# Memory.net
KiCad netlist of a schematic drawn in Altium Designer
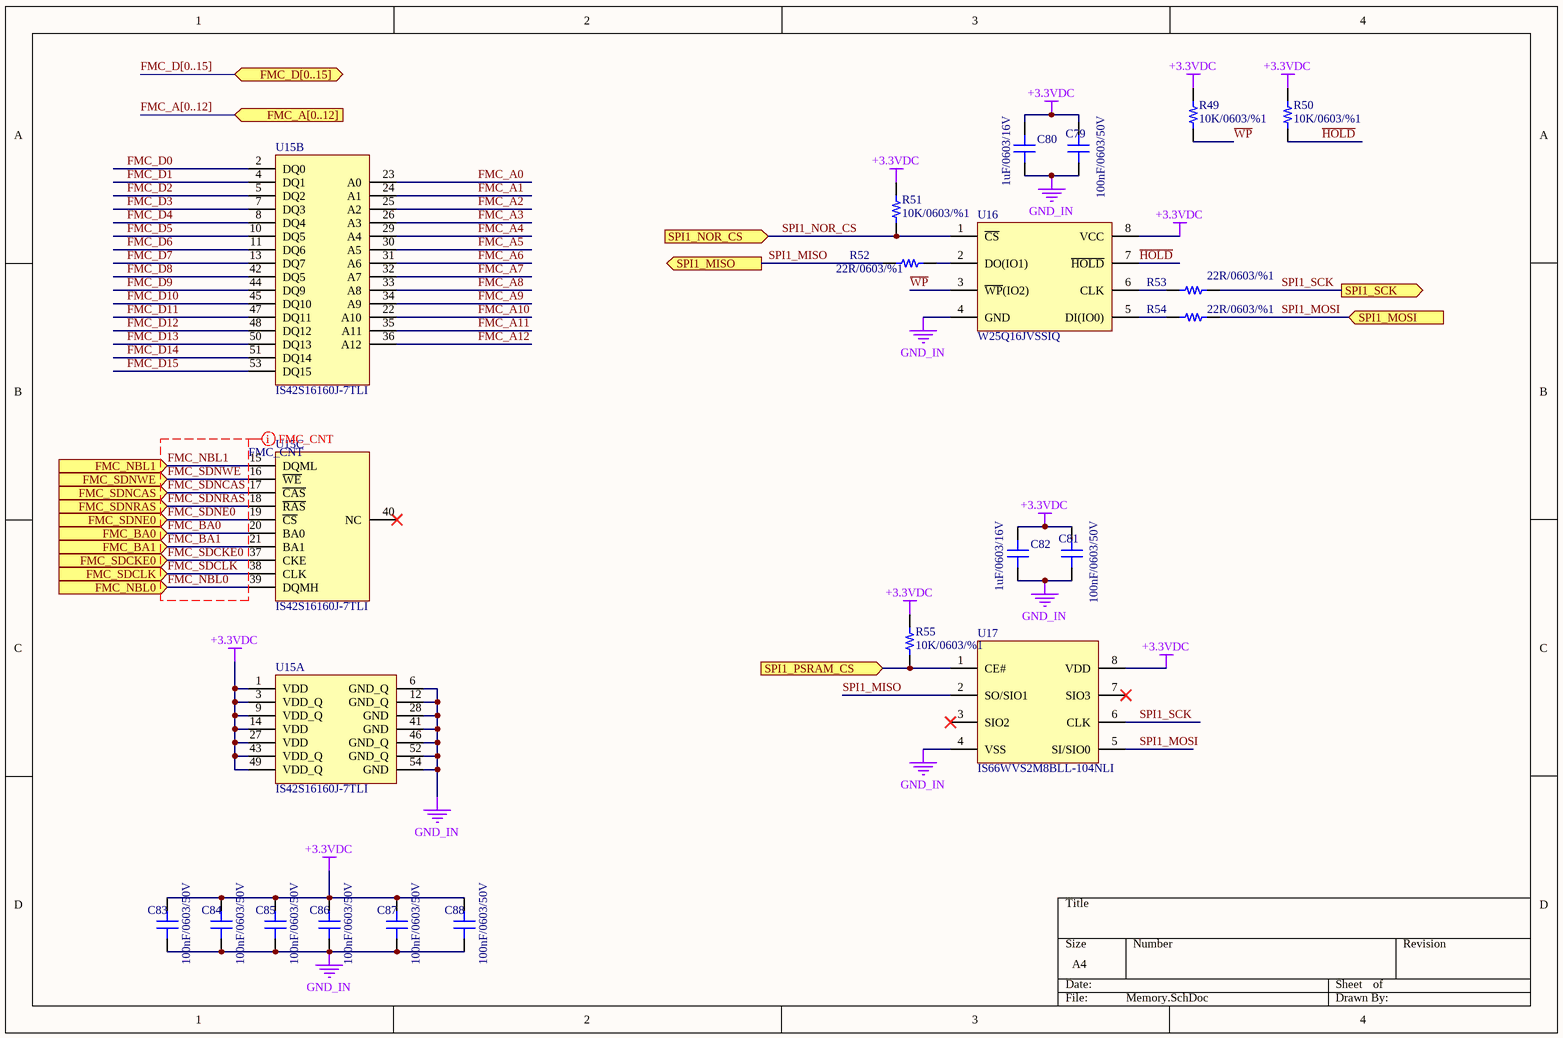
[diagram p0: Memory.SchDoc]

(export (version "E")
  (design (tool "Eeschema 10.0.6"))
  (components
    (comp (ref "C79")
      (value "100nF/0603/50V")
      (footprint "0603_cap")
      (libsource (lib "IM_v1.0") (part "Capacitor"))
    )
    (comp (ref "C80")
      (value "1uF/0603/16V")
      (footprint "0603_cap")
      (libsource (lib "IM_v1.0") (part "Capacitor"))
    )
    (comp (ref "C81")
      (value "100nF/0603/50V")
      (footprint "0603_cap")
      (libsource (lib "IM_v1.0") (part "Capacitor"))
    )
    (comp (ref "C82")
      (value "1uF/0603/16V")
      (footprint "0603_cap")
      (libsource (lib "IM_v1.0") (part "Capacitor"))
    )
    (comp (ref "C83")
      (value "100nF/0603/50V")
      (footprint "0603_cap")
      (libsource (lib "IM_v1.0") (part "Capacitor"))
    )
    (comp (ref "C84")
      (value "100nF/0603/50V")
      (footprint "0603_cap")
      (libsource (lib "IM_v1.0") (part "Capacitor"))
    )
    (comp (ref "C85")
      (value "100nF/0603/50V")
      (footprint "0603_cap")
      (libsource (lib "IM_v1.0") (part "Capacitor"))
    )
    (comp (ref "C86")
      (value "100nF/0603/50V")
      (footprint "0603_cap")
      (libsource (lib "IM_v1.0") (part "Capacitor"))
    )
    (comp (ref "C87")
      (value "100nF/0603/50V")
      (footprint "0603_cap")
      (libsource (lib "IM_v1.0") (part "Capacitor"))
    )
    (comp (ref "C88")
      (value "100nF/0603/50V")
      (footprint "0603_cap")
      (libsource (lib "IM_v1.0") (part "Capacitor"))
    )
    (comp (ref "R49") (value "10K/0603/%1") (footprint "0603_res") (libsource (lib "IM_v1.0") (part "RES")))
    (comp (ref "R50") (value "10K/0603/%1") (footprint "0603_res") (libsource (lib "IM_v1.0") (part "RES")))
    (comp (ref "R51") (value "10K/0603/%1") (footprint "0603_res") (libsource (lib "IM_v1.0") (part "RES")))
    (comp (ref "R52") (value "22R/0603/%1") (footprint "0603_res") (libsource (lib "IM_v1.0") (part "RES")))
    (comp (ref "R53") (value "22R/0603/%1") (footprint "0603_res") (libsource (lib "IM_v1.0") (part "RES")))
    (comp (ref "R54") (value "22R/0603/%1") (footprint "0603_res") (libsource (lib "IM_v1.0") (part "RES")))
    (comp (ref "R55") (value "10K/0603/%1") (footprint "0603_res") (libsource (lib "IM_v1.0") (part "RES")))
    (comp (ref "U15")
      (value "IS42S16160J-7TLI")
      (footprint "TSOP-II-54")
      (description "SDRAM Memory IC 256Mbit Parallel 143 MHz 5.4 ns 54-TSOP II")
      (libsource (lib "IM_v1.0") (part "IS42S16160J-7TLI"))
    )
    (comp (ref "U16")
      (value "W25Q16JVSSIQ")
      (footprint "8-SOIC (0.209\", 5.30mm Width)")
      (description "FLASH - NOR Memory IC 16Mbit SPI - Quad I/O 133 MHz 8-SOIC")
      (libsource (lib "IM_v1.0") (part "W25Q16JVSSIQ"))
    )
    (comp (ref "U17")
      (value "IS66WVS2M8BLL-104NLI")
      (footprint "SOIC-8(3.90MM)")
      (description "PSRAM (Pseudo SRAM) Memory IC 16Mbit SPI, QPI 104 MHz 7 ns 8-SOIC")
      (libsource (lib "IM_v1.0") (part "IS66WVS2M8BLL-104NLI"))
    )
  )
  (nets
    (net (code "1") (name "+3.3VDC") (class "Default")
      (node (ref "C79") (pin "1") (pinfunction "1_1") (pintype "passive"))
      (node (ref "C80") (pin "2") (pinfunction "2_2") (pintype "passive"))
      (node (ref "C81") (pin "1") (pinfunction "1_1") (pintype "passive"))
      (node (ref "C82") (pin "2") (pinfunction "2_2") (pintype "passive"))
      (node (ref "C83") (pin "1") (pinfunction "1_1") (pintype "passive"))
      (node (ref "C84") (pin "1") (pinfunction "1_1") (pintype "passive"))
      (node (ref "C85") (pin "1") (pinfunction "1_1") (pintype "passive"))
      (node (ref "C86") (pin "1") (pinfunction "1_1") (pintype "passive"))
      (node (ref "C87") (pin "1") (pinfunction "1_1") (pintype "passive"))
      (node (ref "C88") (pin "1") (pinfunction "1_1") (pintype "passive"))
      (node (ref "R49") (pin "1") (pinfunction "1_1") (pintype "passive"))
      (node (ref "R50") (pin "1") (pinfunction "1_1") (pintype "passive"))
      (node (ref "R51") (pin "1") (pinfunction "1_1") (pintype "passive"))
      (node (ref "R55") (pin "1") (pinfunction "1_1") (pintype "passive"))
      (node (ref "U15") (pin "1") (pinfunction "VDD_1") (pintype "passive"))
      (node (ref "U15") (pin "14") (pinfunction "VDD_14") (pintype "passive"))
      (node (ref "U15") (pin "27") (pinfunction "VDD_27") (pintype "passive"))
      (node (ref "U15") (pin "3") (pinfunction "VDD_Q_3") (pintype "passive"))
      (node (ref "U15") (pin "43") (pinfunction "VDD_Q_43") (pintype "passive"))
      (node (ref "U15") (pin "49") (pinfunction "VDD_Q_49") (pintype "passive"))
      (node (ref "U15") (pin "9") (pinfunction "VDD_Q_9") (pintype "passive"))
      (node (ref "U16") (pin "8") (pinfunction "VCC_8") (pintype "passive"))
      (node (ref "U17") (pin "8") (pinfunction "VDD_8") (pintype "passive"))
    )
    (net (code "2") (name "/FMC_A0") (class "Default")
      (node (ref "U15") (pin "23") (pinfunction "A0_23") (pintype "passive"))
    )
    (net (code "3") (name "/FMC_A1") (class "Default")
      (node (ref "U15") (pin "24") (pinfunction "A1_24") (pintype "passive"))
    )
    (net (code "4") (name "/FMC_A2") (class "Default")
      (node (ref "U15") (pin "25") (pinfunction "A2_25") (pintype "passive"))
    )
    (net (code "5") (name "/FMC_A3") (class "Default")
      (node (ref "U15") (pin "26") (pinfunction "A3_26") (pintype "passive"))
    )
    (net (code "6") (name "/FMC_A4") (class "Default")
      (node (ref "U15") (pin "29") (pinfunction "A4_29") (pintype "passive"))
    )
    (net (code "7") (name "/FMC_A5") (class "Default")
      (node (ref "U15") (pin "30") (pinfunction "A5_30") (pintype "passive"))
    )
    (net (code "8") (name "/FMC_A6") (class "Default")
      (node (ref "U15") (pin "31") (pinfunction "A6_31") (pintype "passive"))
    )
    (net (code "9") (name "/FMC_A7") (class "Default")
      (node (ref "U15") (pin "32") (pinfunction "A7_32") (pintype "passive"))
    )
    (net (code "10") (name "/FMC_A8") (class "Default")
      (node (ref "U15") (pin "33") (pinfunction "A8_33") (pintype "passive"))
    )
    (net (code "11") (name "/FMC_A9") (class "Default")
      (node (ref "U15") (pin "34") (pinfunction "A9_34") (pintype "passive"))
    )
    (net (code "12") (name "/FMC_A10") (class "Default")
      (node (ref "U15") (pin "22") (pinfunction "A10_22") (pintype "passive"))
    )
    (net (code "13") (name "/FMC_A11") (class "Default")
      (node (ref "U15") (pin "35") (pinfunction "A11_35") (pintype "passive"))
    )
    (net (code "14") (name "/FMC_A12") (class "Default")
      (node (ref "U15") (pin "36") (pinfunction "A12_36") (pintype "passive"))
    )
    (net (code "16") (name "/FMC_BA0") (class "Default")
      (node (ref "U15") (pin "20") (pinfunction "BA0_20") (pintype "passive"))
    )
    (net (code "17") (name "/FMC_BA1") (class "Default")
      (node (ref "U15") (pin "21") (pinfunction "BA1_21") (pintype "passive"))
    )
    (net (code "18") (name "/FMC_D0") (class "Default")
      (node (ref "U15") (pin "2") (pinfunction "DQ0_2") (pintype "passive"))
    )
    (net (code "19") (name "/FMC_D1") (class "Default")
      (node (ref "U15") (pin "4") (pinfunction "DQ1_4") (pintype "passive"))
    )
    (net (code "20") (name "/FMC_D2") (class "Default")
      (node (ref "U15") (pin "5") (pinfunction "DQ2_5") (pintype "passive"))
    )
    (net (code "21") (name "/FMC_D3") (class "Default")
      (node (ref "U15") (pin "7") (pinfunction "DQ3_7") (pintype "passive"))
    )
    (net (code "22") (name "/FMC_D4") (class "Default")
      (node (ref "U15") (pin "8") (pinfunction "DQ4_8") (pintype "passive"))
    )
    (net (code "23") (name "/FMC_D5") (class "Default")
      (node (ref "U15") (pin "10") (pinfunction "DQ5_10") (pintype "passive"))
    )
    (net (code "24") (name "/FMC_D6") (class "Default")
      (node (ref "U15") (pin "11") (pinfunction "DQ6_11") (pintype "passive"))
    )
    (net (code "25") (name "/FMC_D7") (class "Default")
      (node (ref "U15") (pin "13") (pinfunction "DQ7_13") (pintype "passive"))
    )
    (net (code "26") (name "/FMC_D8") (class "Default")
      (node (ref "U15") (pin "42") (pinfunction "DQ5_42") (pintype "passive"))
    )
    (net (code "27") (name "/FMC_D9") (class "Default")
      (node (ref "U15") (pin "44") (pinfunction "DQ9_44") (pintype "passive"))
    )
    (net (code "28") (name "/FMC_D10") (class "Default")
      (node (ref "U15") (pin "45") (pinfunction "DQ10_45") (pintype "passive"))
    )
    (net (code "29") (name "/FMC_D11") (class "Default")
      (node (ref "U15") (pin "47") (pinfunction "DQ11_47") (pintype "passive"))
    )
    (net (code "30") (name "/FMC_D12") (class "Default")
      (node (ref "U15") (pin "48") (pinfunction "DQ12_48") (pintype "passive"))
    )
    (net (code "31") (name "/FMC_D13") (class "Default")
      (node (ref "U15") (pin "50") (pinfunction "DQ13_50") (pintype "passive"))
    )
    (net (code "32") (name "/FMC_D14") (class "Default")
      (node (ref "U15") (pin "51") (pinfunction "DQ14_51") (pintype "passive"))
    )
    (net (code "33") (name "/FMC_D15") (class "Default")
      (node (ref "U15") (pin "53") (pinfunction "DQ15_53") (pintype "passive"))
    )
    (net (code "35") (name "/FMC_NBL0") (class "Default")
      (node (ref "U15") (pin "39") (pinfunction "DQMH_39") (pintype "passive"))
    )
    (net (code "36") (name "/FMC_NBL1") (class "Default")
      (node (ref "U15") (pin "15") (pinfunction "DQML_15") (pintype "passive"))
    )
    (net (code "37") (name "/FMC_SDCKE0") (class "Default")
      (node (ref "U15") (pin "37") (pinfunction "CKE_37") (pintype "passive"))
    )
    (net (code "38") (name "/FMC_SDCLK") (class "Default")
      (node (ref "U15") (pin "38") (pinfunction "CLK_38") (pintype "passive"))
    )
    (net (code "39") (name "/FMC_SDNCAS") (class "Default")
      (node (ref "U15") (pin "17") (pinfunction "~{CAS}_17") (pintype "passive"))
    )
    (net (code "40") (name "/FMC_SDNE0") (class "Default")
      (node (ref "U15") (pin "19") (pinfunction "~{CS}_19") (pintype "passive"))
    )
    (net (code "41") (name "/FMC_SDNRAS") (class "Default")
      (node (ref "U15") (pin "18") (pinfunction "~{RAS}_18") (pintype "passive"))
    )
    (net (code "42") (name "/FMC_SDNWE") (class "Default")
      (node (ref "U15") (pin "16") (pinfunction "~{WE}_16") (pintype "passive"))
    )
    (net (code "43") (name "/SPI1_MISO") (class "Default")
      (node (ref "R52") (pin "1") (pinfunction "1_1") (pintype "passive"))
      (node (ref "U17") (pin "2") (pinfunction "SO/SIO1_2") (pintype "passive"))
    )
    (net (code "44") (name "/SPI1_MOSI") (class "Default")
      (node (ref "R54") (pin "2") (pinfunction "2_2") (pintype "passive"))
      (node (ref "U17") (pin "5") (pinfunction "SI/SIO0_5") (pintype "passive"))
    )
    (net (code "45") (name "/SPI1_NOR_CS") (class "Default")
      (node (ref "R51") (pin "2") (pinfunction "2_2") (pintype "passive"))
      (node (ref "U16") (pin "1") (pinfunction "~{CS}_1") (pintype "passive"))
    )
    (net (code "46") (name "/SPI1_PSRAM_CS") (class "Default")
      (node (ref "R55") (pin "2") (pinfunction "2_2") (pintype "passive"))
      (node (ref "U17") (pin "1") (pinfunction "CE#_1") (pintype "passive"))
    )
    (net (code "47") (name "/SPI1_SCK") (class "Default")
      (node (ref "R53") (pin "2") (pinfunction "2_2") (pintype "passive"))
      (node (ref "U17") (pin "6") (pinfunction "CLK_6") (pintype "passive"))
    )
    (net (code "48") (name "/~{HOLD}") (class "Default")
      (node (ref "R50") (pin "2") (pinfunction "2_2") (pintype "passive"))
      (node (ref "U16") (pin "7") (pinfunction "~{HOLD}_7") (pintype "passive"))
    )
    (net (code "49") (name "/~{WP}") (class "Default")
      (node (ref "R49") (pin "2") (pinfunction "2_2") (pintype "passive"))
      (node (ref "U16") (pin "3") (pinfunction "~{WP}(IO2)_3") (pintype "passive"))
    )
    (net (code "50") (name "GND_IN") (class "Default")
      (node (ref "C79") (pin "2") (pinfunction "2_2") (pintype "passive"))
      (node (ref "C80") (pin "1") (pinfunction "1_1") (pintype "passive"))
      (node (ref "C81") (pin "2") (pinfunction "2_2") (pintype "passive"))
      (node (ref "C82") (pin "1") (pinfunction "1_1") (pintype "passive"))
      (node (ref "C83") (pin "2") (pinfunction "2_2") (pintype "passive"))
      (node (ref "C84") (pin "2") (pinfunction "2_2") (pintype "passive"))
      (node (ref "C85") (pin "2") (pinfunction "2_2") (pintype "passive"))
      (node (ref "C86") (pin "2") (pinfunction "2_2") (pintype "passive"))
      (node (ref "C87") (pin "2") (pinfunction "2_2") (pintype "passive"))
      (node (ref "C88") (pin "2") (pinfunction "2_2") (pintype "passive"))
      (node (ref "U15") (pin "12") (pinfunction "GND_Q_12") (pintype "passive"))
      (node (ref "U15") (pin "28") (pinfunction "GND_28") (pintype "passive"))
      (node (ref "U15") (pin "41") (pinfunction "GND_41") (pintype "passive"))
      (node (ref "U15") (pin "46") (pinfunction "GND_Q_46") (pintype "passive"))
      (node (ref "U15") (pin "52") (pinfunction "GND_Q_52") (pintype "passive"))
      (node (ref "U15") (pin "54") (pinfunction "GND_54") (pintype "passive"))
      (node (ref "U15") (pin "6") (pinfunction "GND_Q_6") (pintype "passive"))
      (node (ref "U16") (pin "4") (pinfunction "GND_4") (pintype "passive"))
      (node (ref "U17") (pin "4") (pinfunction "VSS_4") (pintype "passive"))
    )
    (net (code "51") (name "Net-(U16-CLK)") (class "Default")
      (node (ref "R53") (pin "1") (pinfunction "1_1") (pintype "passive"))
      (node (ref "U16") (pin "6") (pinfunction "CLK_6") (pintype "passive"))
    )
    (net (code "52") (name "Net-(U16-DI(IO0))") (class "Default")
      (node (ref "R54") (pin "1") (pinfunction "1_1") (pintype "passive"))
      (node (ref "U16") (pin "5") (pinfunction "DI(IO0)_5") (pintype "passive"))
    )
    (net (code "53") (name "Net-(U16-DO(IO1))") (class "Default")
      (node (ref "R52") (pin "2") (pinfunction "2_2") (pintype "passive"))
      (node (ref "U16") (pin "2") (pinfunction "DO(IO1)_2") (pintype "passive"))
    )
    (net (code "54") (name "unconnected-(U15C-NC-Pad40)") (class "Default")
      (node (ref "U15") (pin "40") (pinfunction "NC_40") (pintype "passive+no_connect"))
    )
    (net (code "55") (name "unconnected-(U17-SIO2-Pad3)") (class "Default")
      (node (ref "U17") (pin "3") (pinfunction "SIO2_3") (pintype "passive+no_connect"))
    )
    (net (code "56") (name "unconnected-(U17-SIO3-Pad7)") (class "Default")
      (node (ref "U17") (pin "7") (pinfunction "SIO3_7") (pintype "passive+no_connect"))
    )
  )
)
